# ROm-el_HN61256_Adapter_v2.net
KiCad netlist of a schematic drawn in EAGLE
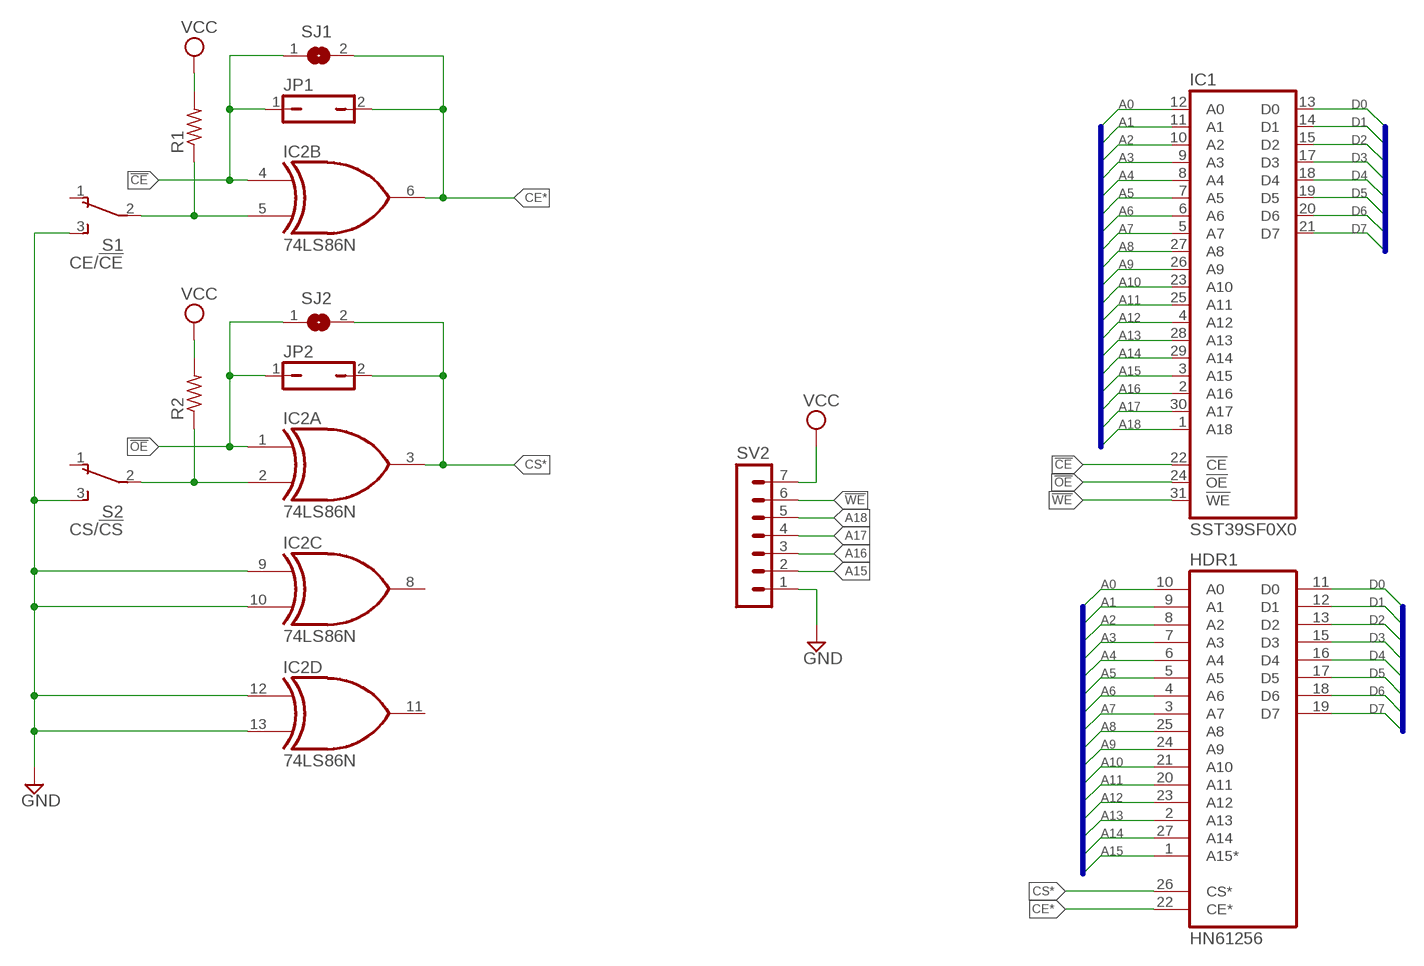
[diagram p0: schematic, sheet 1]

(export (version "E")
  (design (tool "Eeschema 10.0.6"))
  (components
    (comp (ref "HDR1")
      (value "HN61256")
      (footprint "eagle-import:DIL28-6")
      (libsource (lib "eagle-import") (part "HN61256"))
    )
    (comp (ref "IC1")
      (value "SST39SF0X0")
      (footprint "eagle-import:DIL32-RP")
      (libsource (lib "eagle-import") (part "SST39SF040APHR"))
    )
    (comp (ref "IC2")
      (value "74LS86N")
      (footprint "eagle-import:DIL14-RP")
      (libsource (lib "eagle-import") (part "7486NLS"))
    )
    (comp (ref "JP1")
      (value "JP1Q")
      (footprint "eagle-import:JP1")
      (libsource (lib "eagle-import") (part "JP1Q"))
    )
    (comp (ref "JP2")
      (value "JP1Q")
      (footprint "eagle-import:JP1")
      (libsource (lib "eagle-import") (part "JP1Q"))
    )
    (comp (ref "R1")
      (value "R-US_0204/5")
      (footprint "eagle-import:0204_5")
      (libsource (lib "eagle-import") (part "R-US_0204/5"))
    )
    (comp (ref "R2")
      (value "R-US_0204/5")
      (footprint "eagle-import:0204_5")
      (libsource (lib "eagle-import") (part "R-US_0204/5"))
    )
    (comp (ref "S1")
      (value "CE/!CE")
      (footprint "eagle-import:TL3XWO")
      (libsource (lib "eagle-import") (part "TL36WO"))
    )
    (comp (ref "S2")
      (value "CS/!CS")
      (footprint "eagle-import:TL3XWO")
      (libsource (lib "eagle-import") (part "TL36WO"))
    )
    (comp (ref "SJ1") (value "SJ") (footprint "eagle-import:SJ") (libsource (lib "eagle-import") (part "SJ")))
    (comp (ref "SJ2") (value "SJ") (footprint "eagle-import:SJ") (libsource (lib "eagle-import") (part "SJ")))
    (comp (ref "SV2")
      (value "MA07-1")
      (footprint "eagle-import:MA07-1")
      (libsource (lib "eagle-import") (part "MA07-1"))
    )
  )
  (nets
    (net (code "1") (name "/A0") (class "Default")
      (node (ref "HDR1") (pin "10") (pinfunction "A0_10") (pintype "input"))
      (node (ref "IC1") (pin "12") (pinfunction "A0_12") (pintype "input"))
    )
    (net (code "2") (name "/A1") (class "Default")
      (node (ref "HDR1") (pin "9") (pinfunction "A1_9") (pintype "input"))
      (node (ref "IC1") (pin "11") (pinfunction "A1_11") (pintype "input"))
    )
    (net (code "3") (name "/A2") (class "Default")
      (node (ref "HDR1") (pin "8") (pinfunction "A2_8") (pintype "input"))
      (node (ref "IC1") (pin "10") (pinfunction "A2_10") (pintype "input"))
    )
    (net (code "4") (name "/A3") (class "Default")
      (node (ref "HDR1") (pin "7") (pinfunction "A3_7") (pintype "input"))
      (node (ref "IC1") (pin "9") (pinfunction "A3_9") (pintype "input"))
    )
    (net (code "5") (name "/A4") (class "Default")
      (node (ref "HDR1") (pin "6") (pinfunction "A4_6") (pintype "input"))
      (node (ref "IC1") (pin "8") (pinfunction "A4_8") (pintype "input"))
    )
    (net (code "6") (name "/A5") (class "Default")
      (node (ref "HDR1") (pin "5") (pinfunction "A5_5") (pintype "input"))
      (node (ref "IC1") (pin "7") (pinfunction "A5_7") (pintype "input"))
    )
    (net (code "7") (name "/A6") (class "Default")
      (node (ref "HDR1") (pin "4") (pinfunction "A6_4") (pintype "input"))
      (node (ref "IC1") (pin "6") (pinfunction "A6_6") (pintype "input"))
    )
    (net (code "8") (name "/A7") (class "Default")
      (node (ref "HDR1") (pin "3") (pinfunction "A7_3") (pintype "input"))
      (node (ref "IC1") (pin "5") (pinfunction "A7_5") (pintype "input"))
    )
    (net (code "9") (name "/A8") (class "Default")
      (node (ref "HDR1") (pin "25") (pinfunction "A8_25") (pintype "input"))
      (node (ref "IC1") (pin "27") (pinfunction "A8_27") (pintype "input"))
    )
    (net (code "10") (name "/A9") (class "Default")
      (node (ref "HDR1") (pin "24") (pinfunction "A9_24") (pintype "input"))
      (node (ref "IC1") (pin "26") (pinfunction "A9_26") (pintype "input"))
    )
    (net (code "11") (name "/A10") (class "Default")
      (node (ref "HDR1") (pin "21") (pinfunction "A10_21") (pintype "input"))
      (node (ref "IC1") (pin "23") (pinfunction "A10_23") (pintype "input"))
    )
    (net (code "12") (name "/A11") (class "Default")
      (node (ref "HDR1") (pin "20") (pinfunction "A11_20") (pintype "input"))
      (node (ref "IC1") (pin "25") (pinfunction "A11_25") (pintype "input"))
    )
    (net (code "13") (name "/A12") (class "Default")
      (node (ref "HDR1") (pin "23") (pinfunction "A12_23") (pintype "input"))
      (node (ref "IC1") (pin "4") (pinfunction "A12_4") (pintype "input"))
    )
    (net (code "14") (name "/A13") (class "Default")
      (node (ref "HDR1") (pin "2") (pinfunction "A13_2") (pintype "input"))
      (node (ref "IC1") (pin "28") (pinfunction "A13_28") (pintype "input"))
    )
    (net (code "15") (name "/A14") (class "Default")
      (node (ref "HDR1") (pin "27") (pinfunction "A14_27") (pintype "input"))
      (node (ref "IC1") (pin "29") (pinfunction "A14_29") (pintype "input"))
    )
    (net (code "16") (name "/D0") (class "Default")
      (node (ref "HDR1") (pin "11") (pinfunction "D0_11") (pintype "bidirectional"))
      (node (ref "IC1") (pin "13") (pinfunction "D0_13") (pintype "bidirectional"))
    )
    (net (code "17") (name "/D1") (class "Default")
      (node (ref "HDR1") (pin "12") (pinfunction "D1_12") (pintype "bidirectional"))
      (node (ref "IC1") (pin "14") (pinfunction "D1_14") (pintype "bidirectional"))
    )
    (net (code "18") (name "/D2") (class "Default")
      (node (ref "HDR1") (pin "13") (pinfunction "D2_13") (pintype "bidirectional"))
      (node (ref "IC1") (pin "15") (pinfunction "D2_15") (pintype "bidirectional"))
    )
    (net (code "19") (name "/D3") (class "Default")
      (node (ref "HDR1") (pin "15") (pinfunction "D3_15") (pintype "bidirectional"))
      (node (ref "IC1") (pin "17") (pinfunction "D3_17") (pintype "bidirectional"))
    )
    (net (code "20") (name "/D4") (class "Default")
      (node (ref "HDR1") (pin "16") (pinfunction "D4_16") (pintype "bidirectional"))
      (node (ref "IC1") (pin "18") (pinfunction "D4_18") (pintype "bidirectional"))
    )
    (net (code "21") (name "/D5") (class "Default")
      (node (ref "HDR1") (pin "17") (pinfunction "D5_17") (pintype "bidirectional"))
      (node (ref "IC1") (pin "19") (pinfunction "D5_19") (pintype "bidirectional"))
    )
    (net (code "22") (name "/D6") (class "Default")
      (node (ref "HDR1") (pin "18") (pinfunction "D6_18") (pintype "bidirectional"))
      (node (ref "IC1") (pin "20") (pinfunction "D6_20") (pintype "bidirectional"))
    )
    (net (code "23") (name "/D7") (class "Default")
      (node (ref "HDR1") (pin "19") (pinfunction "D7_19") (pintype "bidirectional"))
      (node (ref "IC1") (pin "21") (pinfunction "D7_21") (pintype "bidirectional"))
    )
    (net (code "24") (name "/~{CE}") (class "Default")
      (node (ref "IC1") (pin "22") (pinfunction "~{CE}_22") (pintype "input"))
      (node (ref "IC2") (pin "4") (pinfunction "I0_4") (pintype "input"))
      (node (ref "JP1") (pin "1") (pinfunction "1_1") (pintype "passive"))
      (node (ref "SJ1") (pin "1") (pinfunction "1_1") (pintype "passive"))
    )
    (net (code "25") (name "/~{OE}") (class "Default")
      (node (ref "IC1") (pin "24") (pinfunction "~{OE}_24") (pintype "input"))
      (node (ref "IC2") (pin "1") (pinfunction "I0_1") (pintype "input"))
      (node (ref "JP2") (pin "1") (pinfunction "1_1") (pintype "passive"))
      (node (ref "SJ2") (pin "1") (pinfunction "1_1") (pintype "passive"))
    )
    (net (code "26") (name "/~{WE}") (class "Default")
      (node (ref "IC1") (pin "31") (pinfunction "~{WE}_31") (pintype "input"))
      (node (ref "SV2") (pin "6") (pinfunction "6_6") (pintype "passive"))
    )
    (net (code "27") (name "A15") (class "Default")
      (node (ref "HDR1") (pin "1") (pinfunction "A15*_1") (pintype "input"))
      (node (ref "IC1") (pin "3") (pinfunction "A15_3") (pintype "input"))
      (node (ref "SV2") (pin "2") (pinfunction "2_2") (pintype "passive"))
    )
    (net (code "28") (name "A16") (class "Default")
      (node (ref "IC1") (pin "2") (pinfunction "A16_2") (pintype "input"))
      (node (ref "SV2") (pin "3") (pinfunction "3_3") (pintype "passive"))
    )
    (net (code "29") (name "A17") (class "Default")
      (node (ref "IC1") (pin "30") (pinfunction "A17_30") (pintype "input"))
      (node (ref "SV2") (pin "4") (pinfunction "4_4") (pintype "passive"))
    )
    (net (code "30") (name "A18") (class "Default")
      (node (ref "IC1") (pin "1") (pinfunction "A18_1") (pintype "input"))
      (node (ref "SV2") (pin "5") (pinfunction "5_5") (pintype "passive"))
    )
    (net (code "31") (name "CE*") (class "Default")
      (node (ref "HDR1") (pin "22") (pinfunction "CE*_22") (pintype "input"))
      (node (ref "IC2") (pin "6") (pinfunction "O_6") (pintype "output"))
      (node (ref "JP1") (pin "2") (pinfunction "2_2") (pintype "passive"))
      (node (ref "SJ1") (pin "2") (pinfunction "2_2") (pintype "passive"))
    )
    (net (code "32") (name "CS*") (class "Default")
      (node (ref "HDR1") (pin "26") (pinfunction "CS*_26") (pintype "input"))
      (node (ref "IC2") (pin "3") (pinfunction "O_3") (pintype "output"))
      (node (ref "JP2") (pin "2") (pinfunction "2_2") (pintype "passive"))
      (node (ref "SJ2") (pin "2") (pinfunction "2_2") (pintype "passive"))
    )
    (net (code "33") (name "GND") (class "Default")
      (node (ref "IC2") (pin "10") (pinfunction "I1_10") (pintype "input"))
      (node (ref "IC2") (pin "12") (pinfunction "I0_12") (pintype "input"))
      (node (ref "IC2") (pin "13") (pinfunction "I1_13") (pintype "input"))
      (node (ref "IC2") (pin "9") (pinfunction "I0_9") (pintype "input"))
      (node (ref "S1") (pin "3") (pinfunction "S_3") (pintype "passive"))
      (node (ref "S2") (pin "3") (pinfunction "S_3") (pintype "passive"))
      (node (ref "SV2") (pin "1") (pinfunction "1_1") (pintype "passive"))
    )
    (net (code "34") (name "Net-(IC2A-I1)") (class "Default")
      (node (ref "IC2") (pin "2") (pinfunction "I1_2") (pintype "input"))
      (node (ref "R2") (pin "1") (pinfunction "1_1") (pintype "passive"))
      (node (ref "S2") (pin "2") (pinfunction "P_2") (pintype "passive"))
    )
    (net (code "35") (name "Net-(IC2B-I1)") (class "Default")
      (node (ref "IC2") (pin "5") (pinfunction "I1_5") (pintype "input"))
      (node (ref "R1") (pin "1") (pinfunction "1_1") (pintype "passive"))
      (node (ref "S1") (pin "2") (pinfunction "P_2") (pintype "passive"))
    )
    (net (code "36") (name "VCC") (class "Default")
      (node (ref "R1") (pin "2") (pinfunction "2_2") (pintype "passive"))
      (node (ref "R2") (pin "2") (pinfunction "2_2") (pintype "passive"))
      (node (ref "SV2") (pin "7") (pinfunction "7_7") (pintype "passive"))
    )
    (net (code "37") (name "unconnected-(IC2C-O-Pad8)") (class "Default")
      (node (ref "IC2") (pin "8") (pinfunction "O_8") (pintype "output"))
    )
    (net (code "38") (name "unconnected-(IC2D-O-Pad11)") (class "Default")
      (node (ref "IC2") (pin "11") (pinfunction "O_11") (pintype "output"))
    )
    (net (code "39") (name "unconnected-(S1-O-Pad1)") (class "Default")
      (node (ref "S1") (pin "1") (pinfunction "O_1") (pintype "passive"))
    )
    (net (code "40") (name "unconnected-(S2-O-Pad1)") (class "Default")
      (node (ref "S2") (pin "1") (pinfunction "O_1") (pintype "passive"))
    )
  )
)
